# Power.net
KiCad netlist of a schematic drawn in Altium Designer
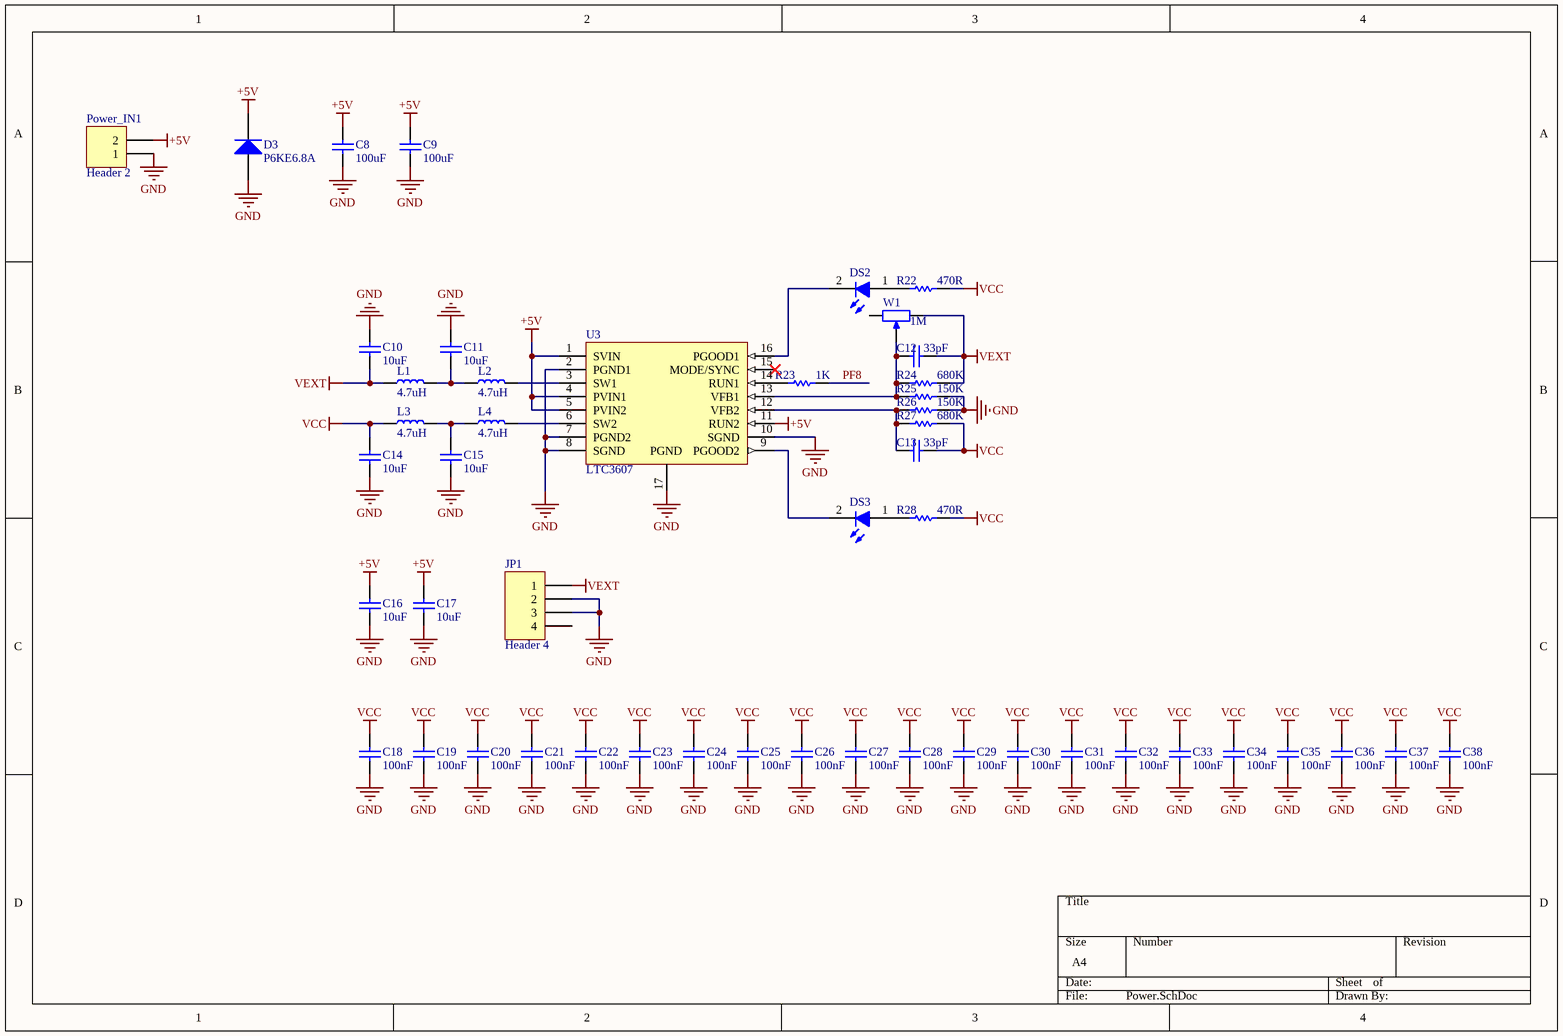
[diagram p0: Power.SchDoc]

(export (version "E")
  (design (tool "Eeschema 10.0.6"))
  (components
    (comp (ref "C8") (value "100uF") (footprint "CAPC3225") (libsource (lib "Slivy's Library") (part "CAP")))
    (comp (ref "C9") (value "100uF") (footprint "CAPC3225") (libsource (lib "Slivy's Library") (part "CAP")))
    (comp (ref "C10")
      (value "10uF")
      (footprint "CAPC0805(2012)75_M")
      (libsource (lib "Slivy's Library") (part "CAP"))
    )
    (comp (ref "C11")
      (value "10uF")
      (footprint "CAPC0805(2012)75_M")
      (libsource (lib "Slivy's Library") (part "CAP"))
    )
    (comp (ref "C12")
      (value "33pF")
      (footprint "CAPC0603(1608)55_M")
      (libsource (lib "Slivy's Library") (part "CAP"))
    )
    (comp (ref "C13")
      (value "33pF")
      (footprint "CAPC0603(1608)55_M")
      (libsource (lib "Slivy's Library") (part "CAP"))
    )
    (comp (ref "C14")
      (value "10uF")
      (footprint "CAPC0805(2012)75_M")
      (libsource (lib "Slivy's Library") (part "CAP"))
    )
    (comp (ref "C15")
      (value "10uF")
      (footprint "CAPC0805(2012)75_M")
      (libsource (lib "Slivy's Library") (part "CAP"))
    )
    (comp (ref "C16")
      (value "10uF")
      (footprint "CAPC0805(2012)75_M")
      (libsource (lib "Slivy's Library") (part "CAP"))
    )
    (comp (ref "C17")
      (value "10uF")
      (footprint "CAPC0805(2012)75_M")
      (libsource (lib "Slivy's Library") (part "CAP"))
    )
    (comp (ref "C18")
      (value "100nF")
      (footprint "CAPC0603(1608)55_M")
      (libsource (lib "Slivy's Library") (part "CAP"))
    )
    (comp (ref "C19")
      (value "100nF")
      (footprint "CAPC0603(1608)55_M")
      (libsource (lib "Slivy's Library") (part "CAP"))
    )
    (comp (ref "C20")
      (value "100nF")
      (footprint "CAPC0603(1608)55_M")
      (libsource (lib "Slivy's Library") (part "CAP"))
    )
    (comp (ref "C21")
      (value "100nF")
      (footprint "CAPC0603(1608)55_M")
      (libsource (lib "Slivy's Library") (part "CAP"))
    )
    (comp (ref "C22")
      (value "100nF")
      (footprint "CAPC0603(1608)55_M")
      (libsource (lib "Slivy's Library") (part "CAP"))
    )
    (comp (ref "C23")
      (value "100nF")
      (footprint "CAPC0603(1608)55_M")
      (libsource (lib "Slivy's Library") (part "CAP"))
    )
    (comp (ref "C24")
      (value "100nF")
      (footprint "CAPC0603(1608)55_M")
      (libsource (lib "Slivy's Library") (part "CAP"))
    )
    (comp (ref "C25")
      (value "100nF")
      (footprint "CAPC0603(1608)55_M")
      (libsource (lib "Slivy's Library") (part "CAP"))
    )
    (comp (ref "C26")
      (value "100nF")
      (footprint "CAPC0603(1608)55_M")
      (libsource (lib "Slivy's Library") (part "CAP"))
    )
    (comp (ref "C27")
      (value "100nF")
      (footprint "CAPC0603(1608)55_M")
      (libsource (lib "Slivy's Library") (part "CAP"))
    )
    (comp (ref "C28")
      (value "100nF")
      (footprint "CAPC0603(1608)55_M")
      (libsource (lib "Slivy's Library") (part "CAP"))
    )
    (comp (ref "C29")
      (value "100nF")
      (footprint "CAPC0603(1608)55_M")
      (libsource (lib "Slivy's Library") (part "CAP"))
    )
    (comp (ref "C30")
      (value "100nF")
      (footprint "CAPC0603(1608)55_M")
      (libsource (lib "Slivy's Library") (part "CAP"))
    )
    (comp (ref "C31")
      (value "100nF")
      (footprint "CAPC0603(1608)55_M")
      (libsource (lib "Slivy's Library") (part "CAP"))
    )
    (comp (ref "C32")
      (value "100nF")
      (footprint "CAPC0603(1608)55_M")
      (libsource (lib "Slivy's Library") (part "CAP"))
    )
    (comp (ref "C33")
      (value "100nF")
      (footprint "CAPC0603(1608)55_M")
      (libsource (lib "Slivy's Library") (part "CAP"))
    )
    (comp (ref "C34")
      (value "100nF")
      (footprint "CAPC0603(1608)55_M")
      (libsource (lib "Slivy's Library") (part "CAP"))
    )
    (comp (ref "C35")
      (value "100nF")
      (footprint "CAPC0603(1608)55_M")
      (libsource (lib "Slivy's Library") (part "CAP"))
    )
    (comp (ref "C36")
      (value "100nF")
      (footprint "CAPC0603(1608)55_M")
      (libsource (lib "Slivy's Library") (part "CAP"))
    )
    (comp (ref "C37")
      (value "100nF")
      (footprint "CAPC0603(1608)55_M")
      (libsource (lib "Slivy's Library") (part "CAP"))
    )
    (comp (ref "C38")
      (value "100nF")
      (footprint "CAPC0603(1608)55_M")
      (libsource (lib "Slivy's Library") (part "CAP"))
    )
    (comp (ref "D3")
      (value "P6KE6.8A")
      (footprint "DO-214AC")
      (libsource (lib "Slivy's ibrary") (part "Diode"))
    )
    (comp (ref "DS2")
      (value "LED-BLUE")
      (footprint "0603LED_BLUE_V")
      (libsource (lib "Slivy's Library") (part "LED-BLUE"))
    )
    (comp (ref "DS3")
      (value "LED-BLUE")
      (footprint "0603LED_BLUE_V")
      (libsource (lib "Slivy's Library") (part "LED-BLUE"))
    )
    (comp (ref "JP1")
      (value "Header 4")
      (footprint "3.96-4-A")
      (description "Header, 4-Pin")
      (fields (field (name "MANUFACTURER") "Generic Components"))
      (libsource (lib "Integrated_Library1") (part "Header 4"))
    )
    (comp (ref "L1") (value "4.7uH") (footprint "CD32") (libsource (lib "Slivy's Library") (part "Inductor")))
    (comp (ref "L2") (value "4.7uH") (footprint "CD32") (libsource (lib "Slivy's Library") (part "Inductor")))
    (comp (ref "L3") (value "4.7uH") (footprint "CD32") (libsource (lib "Slivy's Library") (part "Inductor")))
    (comp (ref "L4") (value "4.7uH") (footprint "CD32") (libsource (lib "Slivy's Library") (part "Inductor")))
    (comp (ref "Power_IN1")
      (value "Header 2")
      (footprint "VH3.96-2-AW")
      (description "Header, 2-Pin")
      (fields (field (name "PUBLISHER") "Altium Limited"))
      (libsource (lib "Miscellaneous Connectors") (part "Header 2"))
    )
    (comp (ref "R22")
      (value "470R")
      (footprint "RESC0603(1608)_M")
      (libsource (lib "Slivy's Library") (part "RES"))
    )
    (comp (ref "R23")
      (value "1K")
      (footprint "RESC0603(1608)_M")
      (libsource (lib "Slivy's Library") (part "RES"))
    )
    (comp (ref "R24")
      (value "680K")
      (footprint "RESC0603(1608)_M")
      (libsource (lib "Slivy's Library") (part "RES"))
    )
    (comp (ref "R25")
      (value "150K")
      (footprint "RESC0603(1608)_M")
      (libsource (lib "Slivy's Library") (part "RES"))
    )
    (comp (ref "R26")
      (value "150K")
      (footprint "RESC0603(1608)_M")
      (libsource (lib "Slivy's Library") (part "RES"))
    )
    (comp (ref "R27")
      (value "680K")
      (footprint "RESC0603(1608)_M")
      (libsource (lib "Slivy's Library") (part "RES"))
    )
    (comp (ref "R28")
      (value "470R")
      (footprint "RESC0603(1608)_M")
      (libsource (lib "Slivy's Library") (part "RES"))
    )
    (comp (ref "U3")
      (value "LTC3607")
      (footprint "MSE16")
      (libsource (lib "Slivy's Library") (part "LTC3607"))
    )
    (comp (ref "W1")
      (value "1M")
      (footprint "VR5")
      (description "Potentiometer")
      (fields
        (field (name "MANUFACTURER") "Generic Components")
        (field (name "PUBLISHER") "Altium Hobart Technology Centre")
      )
      (libsource (lib "Integrated_Library1") (part "RPot2"))
    )
  )
  (nets
    (net (code "1") (name "+5V") (class "Default")
      (node (ref "C16") (pin "2") (pinfunction "2_2") (pintype "passive"))
      (node (ref "C17") (pin "2") (pinfunction "2_2") (pintype "passive"))
      (node (ref "C8") (pin "2") (pinfunction "2_2") (pintype "passive"))
      (node (ref "C9") (pin "2") (pinfunction "2_2") (pintype "passive"))
      (node (ref "D3") (pin "1") (pinfunction "K_1") (pintype "passive"))
      (node (ref "Power_IN1") (pin "2") (pinfunction "2_2") (pintype "passive"))
      (node (ref "U3") (pin "1") (pinfunction "SVIN_1") (pintype "power_in"))
      (node (ref "U3") (pin "11") (pinfunction "RUN2_11") (pintype "input"))
      (node (ref "U3") (pin "4") (pinfunction "PVIN1_4") (pintype "power_in"))
      (node (ref "U3") (pin "5") (pinfunction "PVIN2_5") (pintype "power_in"))
    )
    (net (code "2") (name "/PF8") (class "Default")
      (node (ref "R23") (pin "1") (pinfunction "1_1") (pintype "passive"))
    )
    (net (code "3") (name "GND") (class "Default")
      (node (ref "C10") (pin "2") (pinfunction "2_2") (pintype "passive"))
      (node (ref "C11") (pin "2") (pinfunction "2_2") (pintype "passive"))
      (node (ref "C14") (pin "2") (pinfunction "2_2") (pintype "passive"))
      (node (ref "C15") (pin "2") (pinfunction "2_2") (pintype "passive"))
      (node (ref "C16") (pin "1") (pinfunction "1_1") (pintype "passive"))
      (node (ref "C17") (pin "1") (pinfunction "1_1") (pintype "passive"))
      (node (ref "C18") (pin "1") (pinfunction "1_1") (pintype "passive"))
      (node (ref "C19") (pin "1") (pinfunction "1_1") (pintype "passive"))
      (node (ref "C20") (pin "1") (pinfunction "1_1") (pintype "passive"))
      (node (ref "C21") (pin "1") (pinfunction "1_1") (pintype "passive"))
      (node (ref "C22") (pin "1") (pinfunction "1_1") (pintype "passive"))
      (node (ref "C23") (pin "1") (pinfunction "1_1") (pintype "passive"))
      (node (ref "C24") (pin "1") (pinfunction "1_1") (pintype "passive"))
      (node (ref "C25") (pin "1") (pinfunction "1_1") (pintype "passive"))
      (node (ref "C26") (pin "1") (pinfunction "1_1") (pintype "passive"))
      (node (ref "C27") (pin "1") (pinfunction "1_1") (pintype "passive"))
      (node (ref "C28") (pin "1") (pinfunction "1_1") (pintype "passive"))
      (node (ref "C29") (pin "1") (pinfunction "1_1") (pintype "passive"))
      (node (ref "C30") (pin "1") (pinfunction "1_1") (pintype "passive"))
      (node (ref "C31") (pin "1") (pinfunction "1_1") (pintype "passive"))
      (node (ref "C32") (pin "1") (pinfunction "1_1") (pintype "passive"))
      (node (ref "C33") (pin "1") (pinfunction "1_1") (pintype "passive"))
      (node (ref "C34") (pin "1") (pinfunction "1_1") (pintype "passive"))
      (node (ref "C35") (pin "1") (pinfunction "1_1") (pintype "passive"))
      (node (ref "C36") (pin "1") (pinfunction "1_1") (pintype "passive"))
      (node (ref "C37") (pin "1") (pinfunction "1_1") (pintype "passive"))
      (node (ref "C38") (pin "1") (pinfunction "1_1") (pintype "passive"))
      (node (ref "C8") (pin "1") (pinfunction "1_1") (pintype "passive"))
      (node (ref "C9") (pin "1") (pinfunction "1_1") (pintype "passive"))
      (node (ref "D3") (pin "2") (pinfunction "A_2") (pintype "passive"))
      (node (ref "JP1") (pin "2") (pinfunction "2_2") (pintype "passive"))
      (node (ref "JP1") (pin "3") (pinfunction "3_3") (pintype "passive"))
      (node (ref "Power_IN1") (pin "1") (pinfunction "1_1") (pintype "passive"))
      (node (ref "R25") (pin "1") (pinfunction "1_1") (pintype "passive"))
      (node (ref "R26") (pin "1") (pinfunction "1_1") (pintype "passive"))
      (node (ref "U3") (pin "10") (pinfunction "SGND_10") (pintype "power_in"))
      (node (ref "U3") (pin "17") (pinfunction "PGND_17") (pintype "power_in"))
      (node (ref "U3") (pin "2") (pinfunction "PGND1_2") (pintype "power_in"))
      (node (ref "U3") (pin "7") (pinfunction "PGND2_7") (pintype "power_in"))
      (node (ref "U3") (pin "8") (pinfunction "SGND_8") (pintype "power_in"))
    )
    (net (code "4") (name "Net-(C11-Pad1)") (class "Default")
      (node (ref "C11") (pin "1") (pinfunction "1_1") (pintype "passive"))
      (node (ref "L1") (pin "2") (pinfunction "2_2") (pintype "passive"))
      (node (ref "L2") (pin "1") (pinfunction "1_1") (pintype "passive"))
    )
    (net (code "5") (name "Net-(C15-Pad1)") (class "Default")
      (node (ref "C15") (pin "1") (pinfunction "1_1") (pintype "passive"))
      (node (ref "L3") (pin "2") (pinfunction "2_2") (pintype "passive"))
      (node (ref "L4") (pin "1") (pinfunction "1_1") (pintype "passive"))
    )
    (net (code "6") (name "Net-(DS2-A)") (class "Default")
      (node (ref "DS2") (pin "1") (pinfunction "A_1") (pintype "passive"))
      (node (ref "R22") (pin "2") (pinfunction "2_2") (pintype "passive"))
    )
    (net (code "7") (name "Net-(DS2-K)") (class "Default")
      (node (ref "DS2") (pin "2") (pinfunction "K_2") (pintype "passive"))
      (node (ref "U3") (pin "16") (pinfunction "PGOOD1_16") (pintype "input"))
    )
    (net (code "8") (name "Net-(DS3-A)") (class "Default")
      (node (ref "DS3") (pin "1") (pinfunction "A_1") (pintype "passive"))
      (node (ref "R28") (pin "2") (pinfunction "2_2") (pintype "passive"))
    )
    (net (code "9") (name "Net-(DS3-K)") (class "Default")
      (node (ref "DS3") (pin "2") (pinfunction "K_2") (pintype "passive"))
      (node (ref "U3") (pin "9") (pinfunction "PGOOD2_9") (pintype "output"))
    )
    (net (code "10") (name "Net-(U3-RUN1)") (class "Default")
      (node (ref "R23") (pin "2") (pinfunction "2_2") (pintype "passive"))
      (node (ref "U3") (pin "14") (pinfunction "RUN1_14") (pintype "input"))
    )
    (net (code "11") (name "Net-(U3-SW1)") (class "Default")
      (node (ref "L2") (pin "2") (pinfunction "2_2") (pintype "passive"))
      (node (ref "U3") (pin "3") (pinfunction "SW1_3") (pintype "power_in"))
    )
    (net (code "12") (name "Net-(U3-SW2)") (class "Default")
      (node (ref "L4") (pin "2") (pinfunction "2_2") (pintype "passive"))
      (node (ref "U3") (pin "6") (pinfunction "SW2_6") (pintype "power_in"))
    )
    (net (code "13") (name "Net-(U3-VFB1)") (class "Default")
      (node (ref "C12") (pin "1") (pinfunction "1_1") (pintype "passive"))
      (node (ref "R24") (pin "2") (pinfunction "2_2") (pintype "passive"))
      (node (ref "R25") (pin "2") (pinfunction "2_2") (pintype "passive"))
      (node (ref "U3") (pin "13") (pinfunction "VFB1_13") (pintype "input"))
      (node (ref "W1") (pin "2") (pinfunction "TAP_2") (pintype "passive"))
    )
    (net (code "14") (name "Net-(U3-VFB2)") (class "Default")
      (node (ref "C13") (pin "1") (pinfunction "1_1") (pintype "passive"))
      (node (ref "R26") (pin "2") (pinfunction "2_2") (pintype "passive"))
      (node (ref "R27") (pin "2") (pinfunction "2_2") (pintype "passive"))
      (node (ref "U3") (pin "12") (pinfunction "VFB2_12") (pintype "input"))
    )
    (net (code "15") (name "VCC") (class "Default")
      (node (ref "C13") (pin "2") (pinfunction "2_2") (pintype "passive"))
      (node (ref "C14") (pin "1") (pinfunction "1_1") (pintype "passive"))
      (node (ref "C18") (pin "2") (pinfunction "2_2") (pintype "passive"))
      (node (ref "C19") (pin "2") (pinfunction "2_2") (pintype "passive"))
      (node (ref "C20") (pin "2") (pinfunction "2_2") (pintype "passive"))
      (node (ref "C21") (pin "2") (pinfunction "2_2") (pintype "passive"))
      (node (ref "C22") (pin "2") (pinfunction "2_2") (pintype "passive"))
      (node (ref "C23") (pin "2") (pinfunction "2_2") (pintype "passive"))
      (node (ref "C24") (pin "2") (pinfunction "2_2") (pintype "passive"))
      (node (ref "C25") (pin "2") (pinfunction "2_2") (pintype "passive"))
      (node (ref "C26") (pin "2") (pinfunction "2_2") (pintype "passive"))
      (node (ref "C27") (pin "2") (pinfunction "2_2") (pintype "passive"))
      (node (ref "C28") (pin "2") (pinfunction "2_2") (pintype "passive"))
      (node (ref "C29") (pin "2") (pinfunction "2_2") (pintype "passive"))
      (node (ref "C30") (pin "2") (pinfunction "2_2") (pintype "passive"))
      (node (ref "C31") (pin "2") (pinfunction "2_2") (pintype "passive"))
      (node (ref "C32") (pin "2") (pinfunction "2_2") (pintype "passive"))
      (node (ref "C33") (pin "2") (pinfunction "2_2") (pintype "passive"))
      (node (ref "C34") (pin "2") (pinfunction "2_2") (pintype "passive"))
      (node (ref "C35") (pin "2") (pinfunction "2_2") (pintype "passive"))
      (node (ref "C36") (pin "2") (pinfunction "2_2") (pintype "passive"))
      (node (ref "C37") (pin "2") (pinfunction "2_2") (pintype "passive"))
      (node (ref "C38") (pin "2") (pinfunction "2_2") (pintype "passive"))
      (node (ref "L3") (pin "1") (pinfunction "1_1") (pintype "passive"))
      (node (ref "R22") (pin "1") (pinfunction "1_1") (pintype "passive"))
      (node (ref "R27") (pin "1") (pinfunction "1_1") (pintype "passive"))
      (node (ref "R28") (pin "1") (pinfunction "1_1") (pintype "passive"))
    )
    (net (code "16") (name "VEXT") (class "Default")
      (node (ref "C10") (pin "1") (pinfunction "1_1") (pintype "passive"))
      (node (ref "C12") (pin "2") (pinfunction "2_2") (pintype "passive"))
      (node (ref "JP1") (pin "1") (pinfunction "1_1") (pintype "passive"))
      (node (ref "L1") (pin "1") (pinfunction "1_1") (pintype "passive"))
      (node (ref "R24") (pin "1") (pinfunction "1_1") (pintype "passive"))
      (node (ref "W1") (pin "3") (pinfunction "BOT_3") (pintype "passive"))
    )
    (net (code "17") (name "unconnected-(JP1-Pad4)") (class "Default")
      (node (ref "JP1") (pin "4") (pinfunction "4_4") (pintype "passive"))
    )
    (net (code "18") (name "unconnected-(U3-MODE{slash}SYNC-Pad15)") (class "Default")
      (node (ref "U3") (pin "15") (pinfunction "MODE/SYNC_15") (pintype "input+no_connect"))
    )
    (net (code "19") (name "unconnected-(W1-TOP-Pad1)") (class "Default")
      (node (ref "W1") (pin "1") (pinfunction "TOP_1") (pintype "passive"))
    )
  )
)
